# D_OUTPUT.net
KiCad netlist of a schematic drawn in Altium Designer
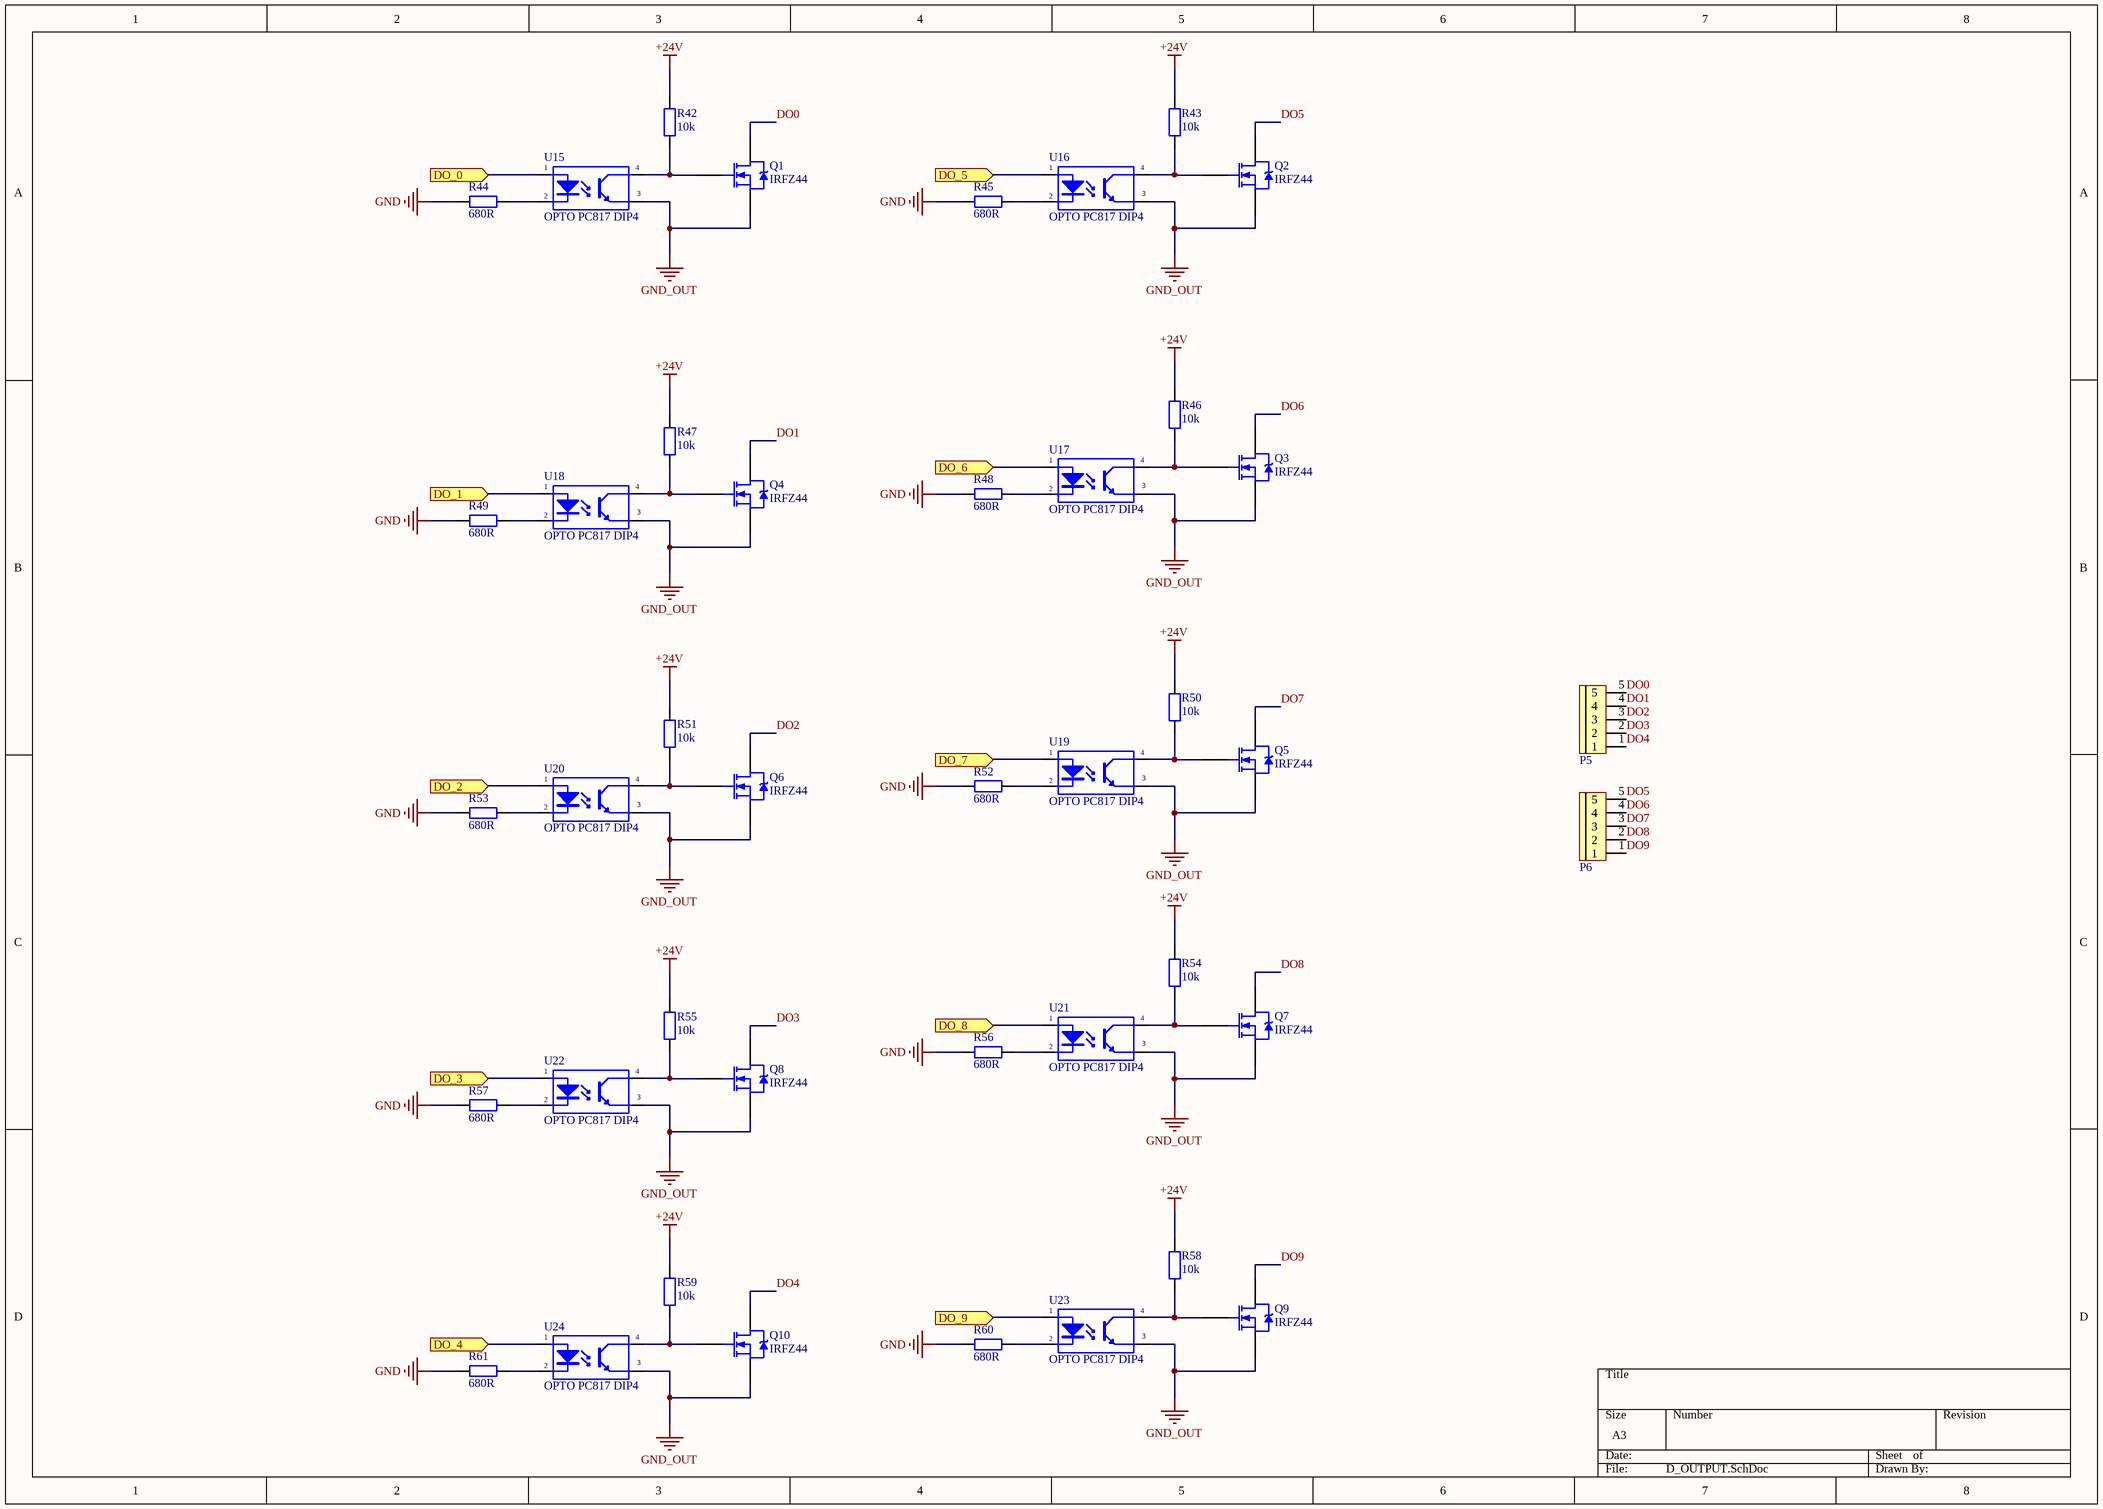
[diagram p0: D_OUTPUT.SchDoc]

(export (version "E")
  (design (tool "Eeschema 10.0.6"))
  (components
    (comp (ref "P5")
      (value "CON 5 EDG5.08")
      (footprint "CON 5 5EDG5.08")
      (description "Cắm")
      (libsource (lib "Altium_Lib_by_KhueNguyenCreator") (part "CON 5 EDG5.08"))
    )
    (comp (ref "P6")
      (value "CON 5 EDG5.08")
      (footprint "CON 5 5EDG5.08")
      (description "Cắm")
      (libsource (lib "Altium_Lib_by_KhueNguyenCreator") (part "CON 5 EDG5.08"))
    )
    (comp (ref "Q1")
      (value "IRFZ44")
      (footprint "TO220")
      (description "TO-220")
      (libsource (lib "Altium_Lib_by_KhueNguyenCreator") (part "FET IRFZ44 DIP"))
    )
    (comp (ref "Q2")
      (value "IRFZ44")
      (footprint "TO220")
      (description "TO-220")
      (libsource (lib "Altium_Lib_by_KhueNguyenCreator") (part "FET IRFZ44 DIP"))
    )
    (comp (ref "Q3")
      (value "IRFZ44")
      (footprint "TO220")
      (description "TO-220")
      (libsource (lib "Altium_Lib_by_KhueNguyenCreator") (part "FET IRFZ44 DIP"))
    )
    (comp (ref "Q4")
      (value "IRFZ44")
      (footprint "TO220")
      (description "TO-220")
      (libsource (lib "Altium_Lib_by_KhueNguyenCreator") (part "FET IRFZ44 DIP"))
    )
    (comp (ref "Q5")
      (value "IRFZ44")
      (footprint "TO220")
      (description "TO-220")
      (libsource (lib "Altium_Lib_by_KhueNguyenCreator") (part "FET IRFZ44 DIP"))
    )
    (comp (ref "Q6")
      (value "IRFZ44")
      (footprint "TO220")
      (description "TO-220")
      (libsource (lib "Altium_Lib_by_KhueNguyenCreator") (part "FET IRFZ44 DIP"))
    )
    (comp (ref "Q7")
      (value "IRFZ44")
      (footprint "TO220")
      (description "TO-220")
      (libsource (lib "Altium_Lib_by_KhueNguyenCreator") (part "FET IRFZ44 DIP"))
    )
    (comp (ref "Q8")
      (value "IRFZ44")
      (footprint "TO220")
      (description "TO-220")
      (libsource (lib "Altium_Lib_by_KhueNguyenCreator") (part "FET IRFZ44 DIP"))
    )
    (comp (ref "Q9")
      (value "IRFZ44")
      (footprint "TO220")
      (description "TO-220")
      (libsource (lib "Altium_Lib_by_KhueNguyenCreator") (part "FET IRFZ44 DIP"))
    )
    (comp (ref "Q10")
      (value "IRFZ44")
      (footprint "TO220")
      (description "TO-220")
      (libsource (lib "Altium_Lib_by_KhueNguyenCreator") (part "FET IRFZ44 DIP"))
    )
    (comp (ref "R42")
      (value "10k")
      (footprint "tro smd 0805")
      (description "Dán")
      (libsource (lib "Altium_Lib_by_KhueNguyenCreator") (part "Tro 0805 1% 10k"))
    )
    (comp (ref "R43")
      (value "10k")
      (footprint "tro smd 0805")
      (description "Dán")
      (libsource (lib "Altium_Lib_by_KhueNguyenCreator") (part "Tro 0805 1% 10k"))
    )
    (comp (ref "R44")
      (value "680R")
      (footprint "tro smd 0805")
      (description "Dán")
      (libsource (lib "Altium_Lib_by_KhueNguyenCreator") (part "Tro 0805 1% 680R"))
    )
    (comp (ref "R45")
      (value "680R")
      (footprint "tro smd 0805")
      (description "Dán")
      (libsource (lib "Altium_Lib_by_KhueNguyenCreator") (part "Tro 0805 1% 680R"))
    )
    (comp (ref "R46")
      (value "10k")
      (footprint "tro smd 0805")
      (description "Dán")
      (libsource (lib "Altium_Lib_by_KhueNguyenCreator") (part "Tro 0805 1% 10k"))
    )
    (comp (ref "R47")
      (value "10k")
      (footprint "tro smd 0805")
      (description "Dán")
      (libsource (lib "Altium_Lib_by_KhueNguyenCreator") (part "Tro 0805 1% 10k"))
    )
    (comp (ref "R48")
      (value "680R")
      (footprint "tro smd 0805")
      (description "Dán")
      (libsource (lib "Altium_Lib_by_KhueNguyenCreator") (part "Tro 0805 1% 680R"))
    )
    (comp (ref "R49")
      (value "680R")
      (footprint "tro smd 0805")
      (description "Dán")
      (libsource (lib "Altium_Lib_by_KhueNguyenCreator") (part "Tro 0805 1% 680R"))
    )
    (comp (ref "R50")
      (value "10k")
      (footprint "tro smd 0805")
      (description "Dán")
      (libsource (lib "Altium_Lib_by_KhueNguyenCreator") (part "Tro 0805 1% 10k"))
    )
    (comp (ref "R51")
      (value "10k")
      (footprint "tro smd 0805")
      (description "Dán")
      (libsource (lib "Altium_Lib_by_KhueNguyenCreator") (part "Tro 0805 1% 10k"))
    )
    (comp (ref "R52")
      (value "680R")
      (footprint "tro smd 0805")
      (description "Dán")
      (libsource (lib "Altium_Lib_by_KhueNguyenCreator") (part "Tro 0805 1% 680R"))
    )
    (comp (ref "R53")
      (value "680R")
      (footprint "tro smd 0805")
      (description "Dán")
      (libsource (lib "Altium_Lib_by_KhueNguyenCreator") (part "Tro 0805 1% 680R"))
    )
    (comp (ref "R54")
      (value "10k")
      (footprint "tro smd 0805")
      (description "Dán")
      (libsource (lib "Altium_Lib_by_KhueNguyenCreator") (part "Tro 0805 1% 10k"))
    )
    (comp (ref "R55")
      (value "10k")
      (footprint "tro smd 0805")
      (description "Dán")
      (libsource (lib "Altium_Lib_by_KhueNguyenCreator") (part "Tro 0805 1% 10k"))
    )
    (comp (ref "R56")
      (value "680R")
      (footprint "tro smd 0805")
      (description "Dán")
      (libsource (lib "Altium_Lib_by_KhueNguyenCreator") (part "Tro 0805 1% 680R"))
    )
    (comp (ref "R57")
      (value "680R")
      (footprint "tro smd 0805")
      (description "Dán")
      (libsource (lib "Altium_Lib_by_KhueNguyenCreator") (part "Tro 0805 1% 680R"))
    )
    (comp (ref "R58")
      (value "10k")
      (footprint "tro smd 0805")
      (description "Dán")
      (libsource (lib "Altium_Lib_by_KhueNguyenCreator") (part "Tro 0805 1% 10k"))
    )
    (comp (ref "R59")
      (value "10k")
      (footprint "tro smd 0805")
      (description "Dán")
      (libsource (lib "Altium_Lib_by_KhueNguyenCreator") (part "Tro 0805 1% 10k"))
    )
    (comp (ref "R60")
      (value "680R")
      (footprint "tro smd 0805")
      (description "Dán")
      (libsource (lib "Altium_Lib_by_KhueNguyenCreator") (part "Tro 0805 1% 680R"))
    )
    (comp (ref "R61")
      (value "680R")
      (footprint "tro smd 0805")
      (description "Dán")
      (libsource (lib "Altium_Lib_by_KhueNguyenCreator") (part "Tro 0805 1% 680R"))
    )
    (comp (ref "U15")
      (value "OPTO PC817 DIP4")
      (footprint "DIP4")
      (description "Single Opto")
      (libsource (lib "Altium_Lib_by_KhueNguyenCreator") (part "OPTO PC817 DIP4"))
    )
    (comp (ref "U16")
      (value "OPTO PC817 DIP4")
      (footprint "DIP4")
      (description "Single Opto")
      (libsource (lib "Altium_Lib_by_KhueNguyenCreator") (part "OPTO PC817 DIP4"))
    )
    (comp (ref "U17")
      (value "OPTO PC817 DIP4")
      (footprint "DIP4")
      (description "Single Opto")
      (libsource (lib "Altium_Lib_by_KhueNguyenCreator") (part "OPTO PC817 DIP4"))
    )
    (comp (ref "U18")
      (value "OPTO PC817 DIP4")
      (footprint "DIP4")
      (description "Single Opto")
      (libsource (lib "Altium_Lib_by_KhueNguyenCreator") (part "OPTO PC817 DIP4"))
    )
    (comp (ref "U19")
      (value "OPTO PC817 DIP4")
      (footprint "DIP4")
      (description "Single Opto")
      (libsource (lib "Altium_Lib_by_KhueNguyenCreator") (part "OPTO PC817 DIP4"))
    )
    (comp (ref "U20")
      (value "OPTO PC817 DIP4")
      (footprint "DIP4")
      (description "Single Opto")
      (libsource (lib "Altium_Lib_by_KhueNguyenCreator") (part "OPTO PC817 DIP4"))
    )
    (comp (ref "U21")
      (value "OPTO PC817 DIP4")
      (footprint "DIP4")
      (description "Single Opto")
      (libsource (lib "Altium_Lib_by_KhueNguyenCreator") (part "OPTO PC817 DIP4"))
    )
    (comp (ref "U22")
      (value "OPTO PC817 DIP4")
      (footprint "DIP4")
      (description "Single Opto")
      (libsource (lib "Altium_Lib_by_KhueNguyenCreator") (part "OPTO PC817 DIP4"))
    )
    (comp (ref "U23")
      (value "OPTO PC817 DIP4")
      (footprint "DIP4")
      (description "Single Opto")
      (libsource (lib "Altium_Lib_by_KhueNguyenCreator") (part "OPTO PC817 DIP4"))
    )
    (comp (ref "U24")
      (value "OPTO PC817 DIP4")
      (footprint "DIP4")
      (description "Single Opto")
      (libsource (lib "Altium_Lib_by_KhueNguyenCreator") (part "OPTO PC817 DIP4"))
    )
  )
  (nets
    (net (code "1") (name "+24V") (class "Default")
      (node (ref "R42") (pin "2") (pinfunction "2_2") (pintype "passive"))
      (node (ref "R43") (pin "2") (pinfunction "2_2") (pintype "passive"))
      (node (ref "R46") (pin "2") (pinfunction "2_2") (pintype "passive"))
      (node (ref "R47") (pin "2") (pinfunction "2_2") (pintype "passive"))
      (node (ref "R50") (pin "2") (pinfunction "2_2") (pintype "passive"))
      (node (ref "R51") (pin "2") (pinfunction "2_2") (pintype "passive"))
      (node (ref "R54") (pin "2") (pinfunction "2_2") (pintype "passive"))
      (node (ref "R55") (pin "2") (pinfunction "2_2") (pintype "passive"))
      (node (ref "R58") (pin "2") (pinfunction "2_2") (pintype "passive"))
      (node (ref "R59") (pin "2") (pinfunction "2_2") (pintype "passive"))
    )
    (net (code "2") (name "/DO0") (class "Default")
      (node (ref "P5") (pin "5") (pinfunction "5_5") (pintype "passive"))
      (node (ref "Q1") (pin "2") (pinfunction "D_2") (pintype "passive"))
    )
    (net (code "3") (name "/DO1") (class "Default")
      (node (ref "P5") (pin "4") (pinfunction "4_4") (pintype "passive"))
      (node (ref "Q4") (pin "2") (pinfunction "D_2") (pintype "passive"))
    )
    (net (code "4") (name "/DO2") (class "Default")
      (node (ref "P5") (pin "3") (pinfunction "3_3") (pintype "passive"))
      (node (ref "Q6") (pin "2") (pinfunction "D_2") (pintype "passive"))
    )
    (net (code "5") (name "/DO3") (class "Default")
      (node (ref "P5") (pin "2") (pinfunction "2_2") (pintype "passive"))
      (node (ref "Q8") (pin "2") (pinfunction "D_2") (pintype "passive"))
    )
    (net (code "6") (name "/DO4") (class "Default")
      (node (ref "P5") (pin "1") (pinfunction "1_1") (pintype "passive"))
      (node (ref "Q10") (pin "2") (pinfunction "D_2") (pintype "passive"))
    )
    (net (code "7") (name "/DO5") (class "Default")
      (node (ref "P6") (pin "5") (pinfunction "5_5") (pintype "passive"))
      (node (ref "Q2") (pin "2") (pinfunction "D_2") (pintype "passive"))
    )
    (net (code "8") (name "/DO6") (class "Default")
      (node (ref "P6") (pin "4") (pinfunction "4_4") (pintype "passive"))
      (node (ref "Q3") (pin "2") (pinfunction "D_2") (pintype "passive"))
    )
    (net (code "9") (name "/DO7") (class "Default")
      (node (ref "P6") (pin "3") (pinfunction "3_3") (pintype "passive"))
      (node (ref "Q5") (pin "2") (pinfunction "D_2") (pintype "passive"))
    )
    (net (code "10") (name "/DO8") (class "Default")
      (node (ref "P6") (pin "2") (pinfunction "2_2") (pintype "passive"))
      (node (ref "Q7") (pin "2") (pinfunction "D_2") (pintype "passive"))
    )
    (net (code "11") (name "/DO9") (class "Default")
      (node (ref "P6") (pin "1") (pinfunction "1_1") (pintype "passive"))
      (node (ref "Q9") (pin "2") (pinfunction "D_2") (pintype "passive"))
    )
    (net (code "12") (name "/DO_0") (class "Default")
      (node (ref "U15") (pin "1") (pinfunction "A_1") (pintype "passive"))
    )
    (net (code "13") (name "/DO_1") (class "Default")
      (node (ref "U18") (pin "1") (pinfunction "A_1") (pintype "passive"))
    )
    (net (code "14") (name "/DO_2") (class "Default")
      (node (ref "U20") (pin "1") (pinfunction "A_1") (pintype "passive"))
    )
    (net (code "15") (name "/DO_3") (class "Default")
      (node (ref "U22") (pin "1") (pinfunction "A_1") (pintype "passive"))
    )
    (net (code "16") (name "/DO_4") (class "Default")
      (node (ref "U24") (pin "1") (pinfunction "A_1") (pintype "passive"))
    )
    (net (code "17") (name "/DO_5") (class "Default")
      (node (ref "U16") (pin "1") (pinfunction "A_1") (pintype "passive"))
    )
    (net (code "18") (name "/DO_6") (class "Default")
      (node (ref "U17") (pin "1") (pinfunction "A_1") (pintype "passive"))
    )
    (net (code "19") (name "/DO_7") (class "Default")
      (node (ref "U19") (pin "1") (pinfunction "A_1") (pintype "passive"))
    )
    (net (code "20") (name "/DO_8") (class "Default")
      (node (ref "U21") (pin "1") (pinfunction "A_1") (pintype "passive"))
    )
    (net (code "21") (name "/DO_9") (class "Default")
      (node (ref "U23") (pin "1") (pinfunction "A_1") (pintype "passive"))
    )
    (net (code "22") (name "GND") (class "Default")
      (node (ref "R44") (pin "1") (pinfunction "1_1") (pintype "passive"))
      (node (ref "R45") (pin "1") (pinfunction "1_1") (pintype "passive"))
      (node (ref "R48") (pin "1") (pinfunction "1_1") (pintype "passive"))
      (node (ref "R49") (pin "1") (pinfunction "1_1") (pintype "passive"))
      (node (ref "R52") (pin "1") (pinfunction "1_1") (pintype "passive"))
      (node (ref "R53") (pin "1") (pinfunction "1_1") (pintype "passive"))
      (node (ref "R56") (pin "1") (pinfunction "1_1") (pintype "passive"))
      (node (ref "R57") (pin "1") (pinfunction "1_1") (pintype "passive"))
      (node (ref "R60") (pin "1") (pinfunction "1_1") (pintype "passive"))
      (node (ref "R61") (pin "1") (pinfunction "1_1") (pintype "passive"))
    )
    (net (code "23") (name "GND_OUT") (class "Default")
      (node (ref "Q1") (pin "3") (pinfunction "S_3") (pintype "passive"))
      (node (ref "Q10") (pin "3") (pinfunction "S_3") (pintype "passive"))
      (node (ref "Q2") (pin "3") (pinfunction "S_3") (pintype "passive"))
      (node (ref "Q3") (pin "3") (pinfunction "S_3") (pintype "passive"))
      (node (ref "Q4") (pin "3") (pinfunction "S_3") (pintype "passive"))
      (node (ref "Q5") (pin "3") (pinfunction "S_3") (pintype "passive"))
      (node (ref "Q6") (pin "3") (pinfunction "S_3") (pintype "passive"))
      (node (ref "Q7") (pin "3") (pinfunction "S_3") (pintype "passive"))
      (node (ref "Q8") (pin "3") (pinfunction "S_3") (pintype "passive"))
      (node (ref "Q9") (pin "3") (pinfunction "S_3") (pintype "passive"))
      (node (ref "U15") (pin "3") (pinfunction "E_3") (pintype "passive"))
      (node (ref "U16") (pin "3") (pinfunction "E_3") (pintype "passive"))
      (node (ref "U17") (pin "3") (pinfunction "E_3") (pintype "passive"))
      (node (ref "U18") (pin "3") (pinfunction "E_3") (pintype "passive"))
      (node (ref "U19") (pin "3") (pinfunction "E_3") (pintype "passive"))
      (node (ref "U20") (pin "3") (pinfunction "E_3") (pintype "passive"))
      (node (ref "U21") (pin "3") (pinfunction "E_3") (pintype "passive"))
      (node (ref "U22") (pin "3") (pinfunction "E_3") (pintype "passive"))
      (node (ref "U23") (pin "3") (pinfunction "E_3") (pintype "passive"))
      (node (ref "U24") (pin "3") (pinfunction "E_3") (pintype "passive"))
    )
    (net (code "24") (name "Net-(Q1-G)") (class "Default")
      (node (ref "Q1") (pin "1") (pinfunction "G_1") (pintype "passive"))
      (node (ref "R42") (pin "1") (pinfunction "1_1") (pintype "passive"))
      (node (ref "U15") (pin "4") (pinfunction "C_4") (pintype "passive"))
    )
    (net (code "25") (name "Net-(Q2-G)") (class "Default")
      (node (ref "Q2") (pin "1") (pinfunction "G_1") (pintype "passive"))
      (node (ref "R43") (pin "1") (pinfunction "1_1") (pintype "passive"))
      (node (ref "U16") (pin "4") (pinfunction "C_4") (pintype "passive"))
    )
    (net (code "26") (name "Net-(Q3-G)") (class "Default")
      (node (ref "Q3") (pin "1") (pinfunction "G_1") (pintype "passive"))
      (node (ref "R46") (pin "1") (pinfunction "1_1") (pintype "passive"))
      (node (ref "U17") (pin "4") (pinfunction "C_4") (pintype "passive"))
    )
    (net (code "27") (name "Net-(Q4-G)") (class "Default")
      (node (ref "Q4") (pin "1") (pinfunction "G_1") (pintype "passive"))
      (node (ref "R47") (pin "1") (pinfunction "1_1") (pintype "passive"))
      (node (ref "U18") (pin "4") (pinfunction "C_4") (pintype "passive"))
    )
    (net (code "28") (name "Net-(Q5-G)") (class "Default")
      (node (ref "Q5") (pin "1") (pinfunction "G_1") (pintype "passive"))
      (node (ref "R50") (pin "1") (pinfunction "1_1") (pintype "passive"))
      (node (ref "U19") (pin "4") (pinfunction "C_4") (pintype "passive"))
    )
    (net (code "29") (name "Net-(Q6-G)") (class "Default")
      (node (ref "Q6") (pin "1") (pinfunction "G_1") (pintype "passive"))
      (node (ref "R51") (pin "1") (pinfunction "1_1") (pintype "passive"))
      (node (ref "U20") (pin "4") (pinfunction "C_4") (pintype "passive"))
    )
    (net (code "30") (name "Net-(Q7-G)") (class "Default")
      (node (ref "Q7") (pin "1") (pinfunction "G_1") (pintype "passive"))
      (node (ref "R54") (pin "1") (pinfunction "1_1") (pintype "passive"))
      (node (ref "U21") (pin "4") (pinfunction "C_4") (pintype "passive"))
    )
    (net (code "31") (name "Net-(Q8-G)") (class "Default")
      (node (ref "Q8") (pin "1") (pinfunction "G_1") (pintype "passive"))
      (node (ref "R55") (pin "1") (pinfunction "1_1") (pintype "passive"))
      (node (ref "U22") (pin "4") (pinfunction "C_4") (pintype "passive"))
    )
    (net (code "32") (name "Net-(Q9-G)") (class "Default")
      (node (ref "Q9") (pin "1") (pinfunction "G_1") (pintype "passive"))
      (node (ref "R58") (pin "1") (pinfunction "1_1") (pintype "passive"))
      (node (ref "U23") (pin "4") (pinfunction "C_4") (pintype "passive"))
    )
    (net (code "33") (name "Net-(Q10-G)") (class "Default")
      (node (ref "Q10") (pin "1") (pinfunction "G_1") (pintype "passive"))
      (node (ref "R59") (pin "1") (pinfunction "1_1") (pintype "passive"))
      (node (ref "U24") (pin "4") (pinfunction "C_4") (pintype "passive"))
    )
    (net (code "34") (name "Net-(U15-K)") (class "Default")
      (node (ref "R44") (pin "2") (pinfunction "2_2") (pintype "passive"))
      (node (ref "U15") (pin "2") (pinfunction "K_2") (pintype "passive"))
    )
    (net (code "35") (name "Net-(U16-K)") (class "Default")
      (node (ref "R45") (pin "2") (pinfunction "2_2") (pintype "passive"))
      (node (ref "U16") (pin "2") (pinfunction "K_2") (pintype "passive"))
    )
    (net (code "36") (name "Net-(U17-K)") (class "Default")
      (node (ref "R48") (pin "2") (pinfunction "2_2") (pintype "passive"))
      (node (ref "U17") (pin "2") (pinfunction "K_2") (pintype "passive"))
    )
    (net (code "37") (name "Net-(U18-K)") (class "Default")
      (node (ref "R49") (pin "2") (pinfunction "2_2") (pintype "passive"))
      (node (ref "U18") (pin "2") (pinfunction "K_2") (pintype "passive"))
    )
    (net (code "38") (name "Net-(U19-K)") (class "Default")
      (node (ref "R52") (pin "2") (pinfunction "2_2") (pintype "passive"))
      (node (ref "U19") (pin "2") (pinfunction "K_2") (pintype "passive"))
    )
    (net (code "39") (name "Net-(U20-K)") (class "Default")
      (node (ref "R53") (pin "2") (pinfunction "2_2") (pintype "passive"))
      (node (ref "U20") (pin "2") (pinfunction "K_2") (pintype "passive"))
    )
    (net (code "40") (name "Net-(U21-K)") (class "Default")
      (node (ref "R56") (pin "2") (pinfunction "2_2") (pintype "passive"))
      (node (ref "U21") (pin "2") (pinfunction "K_2") (pintype "passive"))
    )
    (net (code "41") (name "Net-(U22-K)") (class "Default")
      (node (ref "R57") (pin "2") (pinfunction "2_2") (pintype "passive"))
      (node (ref "U22") (pin "2") (pinfunction "K_2") (pintype "passive"))
    )
    (net (code "42") (name "Net-(U23-K)") (class "Default")
      (node (ref "R60") (pin "2") (pinfunction "2_2") (pintype "passive"))
      (node (ref "U23") (pin "2") (pinfunction "K_2") (pintype "passive"))
    )
    (net (code "43") (name "Net-(U24-K)") (class "Default")
      (node (ref "R61") (pin "2") (pinfunction "2_2") (pintype "passive"))
      (node (ref "U24") (pin "2") (pinfunction "K_2") (pintype "passive"))
    )
  )
)
